# Monitor2.net
KiCad netlist of a schematic drawn in EAGLE
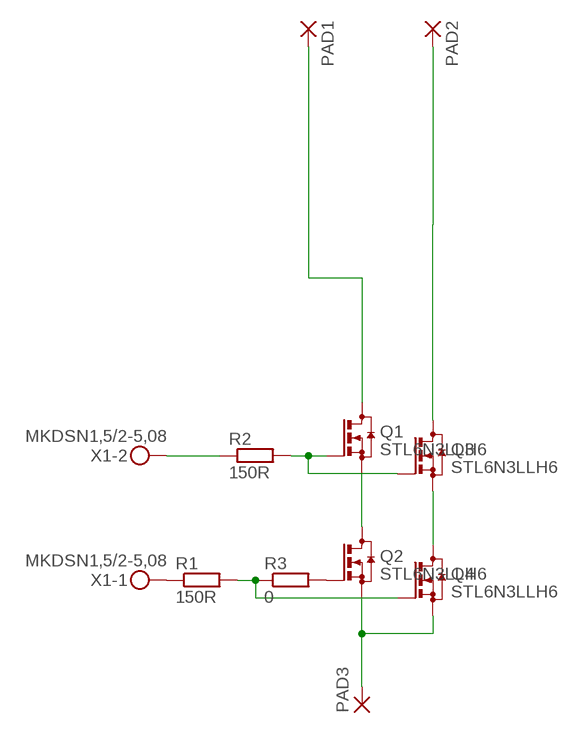
[diagram p0: schematic, sheet 1]

(export (version "E")
  (design (tool "Eeschema 10.0.6"))
  (components
    (comp (ref "PAD1")
      (value "3,81/1,4")
      (footprint "eagle-import:3,81_1,4")
      (libsource (lib "eagle-import") (part "3,81/1,4"))
    )
    (comp (ref "PAD2")
      (value "3,81/1,4")
      (footprint "eagle-import:3,81_1,4")
      (libsource (lib "eagle-import") (part "3,81/1,4"))
    )
    (comp (ref "PAD3")
      (value "3,81/1,4")
      (footprint "eagle-import:3,81_1,4")
      (libsource (lib "eagle-import") (part "3,81/1,4"))
    )
    (comp (ref "Q1")
      (value "STL6N3LLH6")
      (footprint "eagle-import:POWERFLAT-2X2")
      (libsource (lib "eagle-import") (part "STL6N3LLH6"))
    )
    (comp (ref "Q2")
      (value "STL6N3LLH6")
      (footprint "eagle-import:POWERFLAT-2X2")
      (libsource (lib "eagle-import") (part "STL6N3LLH6"))
    )
    (comp (ref "Q3")
      (value "STL6N3LLH6")
      (footprint "eagle-import:POWERFLAT-2X2")
      (libsource (lib "eagle-import") (part "STL6N3LLH6"))
    )
    (comp (ref "Q4")
      (value "STL6N3LLH6")
      (footprint "eagle-import:POWERFLAT-2X2")
      (libsource (lib "eagle-import") (part "STL6N3LLH6"))
    )
    (comp (ref "R1")
      (value "150R")
      (footprint "eagle-import:R1206")
      (libsource (lib "eagle-import") (part "R-EU_R1206"))
    )
    (comp (ref "R2")
      (value "150R")
      (footprint "eagle-import:R1206")
      (libsource (lib "eagle-import") (part "R-EU_R1206"))
    )
    (comp (ref "R3")
      (value "0")
      (footprint "eagle-import:R1206")
      (libsource (lib "eagle-import") (part "R-EU_R1206"))
    )
    (comp (ref "X1")
      (value "MKDSN1,5/2-5,08")
      (footprint "eagle-import:MKDSN1,5_2-5,08")
      (libsource (lib "eagle-import") (part "MKDSN1,5/2-5,08"))
    )
  )
  (nets
    (net (code "1") (name "Net-(PAD1-P)") (class "Default")
      (node (ref "PAD1") (pin "1") (pinfunction "P_1") (pintype "passive"))
      (node (ref "Q1") (pin "1D") (pinfunction "D_1D") (pintype "passive"))
      (node (ref "Q1") (pin "2D") (pinfunction "D_2D") (pintype "passive"))
      (node (ref "Q1") (pin "5D") (pinfunction "D_5D") (pintype "passive"))
      (node (ref "Q1") (pin "6D") (pinfunction "D_6D") (pintype "passive"))
      (node (ref "Q1") (pin "D") (pinfunction "D_D") (pintype "passive"))
    )
    (net (code "2") (name "Net-(PAD2-P)") (class "Default")
      (node (ref "PAD2") (pin "1") (pinfunction "P_1") (pintype "passive"))
      (node (ref "Q3") (pin "1D") (pinfunction "D_1D") (pintype "passive"))
      (node (ref "Q3") (pin "2D") (pinfunction "D_2D") (pintype "passive"))
      (node (ref "Q3") (pin "5D") (pinfunction "D_5D") (pintype "passive"))
      (node (ref "Q3") (pin "6D") (pinfunction "D_6D") (pintype "passive"))
      (node (ref "Q3") (pin "D") (pinfunction "D_D") (pintype "passive"))
    )
    (net (code "3") (name "Net-(PAD3-P)") (class "Default")
      (node (ref "PAD3") (pin "1") (pinfunction "P_1") (pintype "passive"))
      (node (ref "Q2") (pin "4S") (pinfunction "S_4S") (pintype "passive"))
      (node (ref "Q2") (pin "S") (pinfunction "S_S") (pintype "passive"))
      (node (ref "Q4") (pin "4S") (pinfunction "S_4S") (pintype "passive"))
      (node (ref "Q4") (pin "S") (pinfunction "S_S") (pintype "passive"))
    )
    (net (code "4") (name "Net-(Q1-G)") (class "Default")
      (node (ref "Q1") (pin "3G") (pinfunction "G_3G") (pintype "passive"))
      (node (ref "Q3") (pin "3G") (pinfunction "G_3G") (pintype "passive"))
      (node (ref "R2") (pin "2") (pinfunction "2_2") (pintype "passive"))
    )
    (net (code "5") (name "Net-(Q1-PadS)") (class "Default")
      (node (ref "Q1") (pin "4S") (pinfunction "S_4S") (pintype "passive"))
      (node (ref "Q1") (pin "S") (pinfunction "S_S") (pintype "passive"))
      (node (ref "Q2") (pin "1D") (pinfunction "D_1D") (pintype "passive"))
      (node (ref "Q2") (pin "2D") (pinfunction "D_2D") (pintype "passive"))
      (node (ref "Q2") (pin "5D") (pinfunction "D_5D") (pintype "passive"))
      (node (ref "Q2") (pin "6D") (pinfunction "D_6D") (pintype "passive"))
      (node (ref "Q2") (pin "D") (pinfunction "D_D") (pintype "passive"))
    )
    (net (code "6") (name "Net-(Q2-G)") (class "Default")
      (node (ref "Q2") (pin "3G") (pinfunction "G_3G") (pintype "passive"))
      (node (ref "R3") (pin "2") (pinfunction "2_2") (pintype "passive"))
    )
    (net (code "7") (name "Net-(Q3-PadS)") (class "Default")
      (node (ref "Q3") (pin "4S") (pinfunction "S_4S") (pintype "passive"))
      (node (ref "Q3") (pin "S") (pinfunction "S_S") (pintype "passive"))
      (node (ref "Q4") (pin "1D") (pinfunction "D_1D") (pintype "passive"))
      (node (ref "Q4") (pin "2D") (pinfunction "D_2D") (pintype "passive"))
      (node (ref "Q4") (pin "5D") (pinfunction "D_5D") (pintype "passive"))
      (node (ref "Q4") (pin "6D") (pinfunction "D_6D") (pintype "passive"))
      (node (ref "Q4") (pin "D") (pinfunction "D_D") (pintype "passive"))
    )
    (net (code "8") (name "Net-(Q4-G)") (class "Default")
      (node (ref "Q4") (pin "3G") (pinfunction "G_3G") (pintype "passive"))
      (node (ref "R1") (pin "2") (pinfunction "2_2") (pintype "passive"))
      (node (ref "R3") (pin "1") (pinfunction "1_1") (pintype "passive"))
    )
    (net (code "9") (name "Net-(X1A-KL)") (class "Default")
      (node (ref "R1") (pin "1") (pinfunction "1_1") (pintype "passive"))
      (node (ref "X1") (pin "1") (pinfunction "KL_1") (pintype "passive"))
    )
    (net (code "10") (name "Net-(X1B-KL)") (class "Default")
      (node (ref "R2") (pin "1") (pinfunction "1_1") (pintype "passive"))
      (node (ref "X1") (pin "2") (pinfunction "KL_2") (pintype "passive"))
    )
  )
)
